# DO.net
KiCad netlist of a schematic drawn in Altium Designer
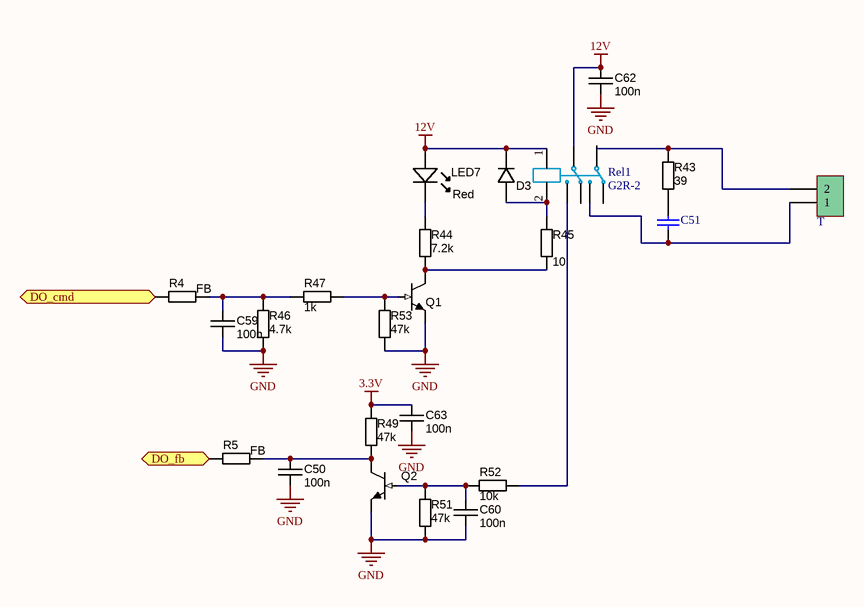
[diagram p0: DO.SchDoc]

(export (version "E")
  (design (tool "Eeschema 10.0.6"))
  (components
    (comp (ref "C50")
      (value "100n")
      (footprint "CAPC1608X90N")
      (description "Capacitor 0603")
      (fields (field (name "TOLERANCE") "±10%"))
      (libsource (lib "PBL - Capacitors") (part "CAPC_1n_0603_X7R_100V_10%"))
    )
    (comp (ref "C51")
      (value "~")
      (footprint "CAP14MM")
      (description "X1Y2 capacitor")
      (fields (field (name "PUBLISHER") "Altium Limited"))
      (libsource (lib "Miscellaneous Devices") (part "Cap Semi"))
    )
    (comp (ref "C59")
      (value "100n")
      (footprint "CAPC1608X90N")
      (description "Capacitor 0603")
      (fields (field (name "TOLERANCE") "±10%"))
      (libsource (lib "PBL - Capacitors") (part "CAPC_1n_0603_X7R_100V_10%"))
    )
    (comp (ref "C60")
      (value "100n")
      (footprint "CAPC1608X90N")
      (description "Capacitor 0603")
      (fields (field (name "TOLERANCE") "±10%"))
      (libsource (lib "PBL - Capacitors") (part "CAPC_1n_0603_X7R_100V_10%"))
    )
    (comp (ref "C62")
      (value "100n")
      (footprint "CAPC1608X90N")
      (description "Capacitor 0603")
      (fields (field (name "TOLERANCE") "±10%"))
      (libsource (lib "PBL - Capacitors") (part "CAPC_1n_0603_X7R_100V_10%"))
    )
    (comp (ref "C63")
      (value "100n")
      (footprint "CAPC1608X90N")
      (description "Capacitor 0603")
      (fields (field (name "TOLERANCE") "±10%"))
      (libsource (lib "PBL - Capacitors") (part "CAPC_1n_0603_X7R_100V_10%"))
    )
    (comp (ref "D3")
      (value "~")
      (footprint "SOD80, LL-34")
      (description "1n4148 minimelf")
      (libsource (lib "PBL - Diodes") (part "DIODE_100V_500mW_MELF"))
    )
    (comp (ref "LED7")
      (value "Red")
      (footprint "LED-0805-K")
      (description "LED 0805 Red")
      (fields (field (name "Comment") "LED B"))
      (libsource (lib "PBL - Light Sources") (part "LED_SMD_Green_0805_6mcd"))
    )
    (comp (ref "Q1")
      (value "~")
      (footprint "SOT-23_N")
      (description "BC817")
      (libsource (lib "PBL - Transistors") (part "NPN_MMBT2222A"))
    )
    (comp (ref "Q2")
      (value "~")
      (footprint "SOT-23_N")
      (description "BC817")
      (libsource (lib "PBL - Transistors") (part "NPN_MMBT2222A"))
    )
    (comp (ref "R4")
      (value "FB")
      (footprint "RESC1608X55N")
      (description "Resistor 0603")
      (fields (field (name "TOLERANCE") "±5%"))
      (libsource (lib "PBL - Resistors") (part "RES_2K2_0603_5%"))
    )
    (comp (ref "R5")
      (value "FB")
      (footprint "RESC1608X55N")
      (description "Resistor 0603")
      (fields (field (name "TOLERANCE") "±5%"))
      (libsource (lib "PBL - Resistors") (part "RES_2K2_0603_5%"))
    )
    (comp (ref "R43")
      (value "39")
      (footprint "RESTH_AXIAL-0.4")
      (description "Resistor .25w dip")
      (fields (field (name "TOLERANCE") "±5%"))
      (libsource (lib "PBL - Resistors") (part "RES_1K5_Axial_0.5W_5%"))
    )
    (comp (ref "R44")
      (value "7.2k")
      (footprint "RESC1608X55N")
      (description "Resistor 0603")
      (fields (field (name "TOLERANCE") "±5%"))
      (libsource (lib "") (part "RES_2K2_0603_5%_1"))
    )
    (comp (ref "R45")
      (value "10")
      (footprint "RESC3216X70N")
      (description "Resistor 1206")
      (fields (field (name "TOLERANCE") "±1%"))
      (libsource (lib "PBL - Resistors") (part "RES_1R_1206_1%"))
    )
    (comp (ref "R46")
      (value "4.7k")
      (footprint "RESC1608X55N")
      (description "Resistor 0603")
      (fields (field (name "TOLERANCE") "±5%"))
      (libsource (lib "") (part "RES_2K2_0603_5%_2"))
    )
    (comp (ref "R47")
      (value "1k")
      (footprint "RESC1608X55N")
      (description "Resistor 0603")
      (fields (field (name "TOLERANCE") "±5%"))
      (libsource (lib "PBL - Resistors") (part "RES_2K2_0603_5%"))
    )
    (comp (ref "R49")
      (value "47k")
      (footprint "RESC1608X55N")
      (description "Resistor 0603")
      (fields (field (name "TOLERANCE") "±5%"))
      (libsource (lib "PBL - Resistors") (part "RES_2K2_0603_5%"))
    )
    (comp (ref "R51")
      (value "47k")
      (footprint "RESC1608X55N")
      (description "Resistor 0603")
      (fields (field (name "TOLERANCE") "±5%"))
      (libsource (lib "PBL - Resistors") (part "RES_2K2_0603_5%"))
    )
    (comp (ref "R52")
      (value "10k")
      (footprint "RESC1608X55N")
      (description "Resistor 0603")
      (fields (field (name "TOLERANCE") "±5%"))
      (libsource (lib "") (part "RES_2K2_0603_5%_1"))
    )
    (comp (ref "R53")
      (value "47k")
      (footprint "RESC1608X55N")
      (description "Resistor 0603")
      (fields (field (name "TOLERANCE") "±5%"))
      (libsource (lib "PBL - Resistors") (part "RES_2K2_0603_5%"))
    )
    (comp (ref "Rel1")
      (value "G2R-2")
      (footprint "relay_G2R_2")
      (libsource (lib "sorour") (part "relay_G2R_2"))
    )
    (comp (ref "T")
      (value "Phoenix terminal 2 pin")
      (footprint "phoenix terminal 2")
      (description "Terminal 2 Pin")
      (fields (field (name "DESIGNER") "Seyed Mohsen Ghasemain") (field (name "E-MAIL") "picpars@gmail.com"))
      (libsource (lib "PicPars.com_usefully_Library") (part "Phoenix terminal 2"))
    )
  )
  (nets
    (net (code "1") (name "/DO_cmd") (class "Default")
      (node (ref "R4") (pin "1") (pinfunction "1_1") (pintype "passive"))
    )
    (net (code "2") (name "/DO_fb") (class "Default")
      (node (ref "R5") (pin "1") (pinfunction "1_1") (pintype "passive"))
    )
    (net (code "3") (name "3.3V") (class "Default")
      (node (ref "C63") (pin "2") (pintype "passive"))
      (node (ref "R49") (pin "2") (pinfunction "2_2") (pintype "passive"))
    )
    (net (code "4") (name "12V") (class "Default")
      (node (ref "C62") (pin "2") (pintype "passive"))
      (node (ref "D3") (pin "K") (pinfunction "K_K") (pintype "passive"))
      (node (ref "LED7") (pin "A") (pinfunction "A_A") (pintype "passive"))
      (node (ref "Rel1") (pin "1") (pintype "passive"))
      (node (ref "Rel1") (pin "3") (pintype "passive"))
    )
    (net (code "5") (name "GND") (class "Default")
      (node (ref "C50") (pin "1") (pintype "passive"))
      (node (ref "C59") (pin "1") (pintype "passive"))
      (node (ref "C60") (pin "1") (pintype "passive"))
      (node (ref "C62") (pin "1") (pintype "passive"))
      (node (ref "C63") (pin "1") (pintype "passive"))
      (node (ref "Q1") (pin "2") (pinfunction "E_2") (pintype "passive"))
      (node (ref "Q2") (pin "2") (pinfunction "E_2") (pintype "passive"))
      (node (ref "R46") (pin "1") (pinfunction "1_1") (pintype "passive"))
      (node (ref "R51") (pin "1") (pinfunction "1_1") (pintype "passive"))
      (node (ref "R53") (pin "1") (pinfunction "1_1") (pintype "passive"))
    )
    (net (code "6") (name "Net-(C51-Pad1)") (class "Default")
      (node (ref "C51") (pin "1") (pinfunction "1_1") (pintype "passive"))
      (node (ref "R43") (pin "2") (pinfunction "2_2") (pintype "passive"))
    )
    (net (code "7") (name "Net-(C51-Pad2)") (class "Default")
      (node (ref "C51") (pin "2") (pinfunction "2_2") (pintype "passive"))
      (node (ref "Rel1") (pin "7") (pintype "passive"))
      (node (ref "T") (pin "1") (pinfunction "1_1") (pintype "passive"))
    )
    (net (code "8") (name "Net-(C59-Pad2)") (class "Default")
      (node (ref "C59") (pin "2") (pintype "passive"))
      (node (ref "R4") (pin "2") (pinfunction "2_2") (pintype "passive"))
      (node (ref "R46") (pin "2") (pinfunction "2_2") (pintype "passive"))
      (node (ref "R47") (pin "1") (pinfunction "1_1") (pintype "passive"))
    )
    (net (code "9") (name "Net-(D3-PadA)") (class "Default")
      (node (ref "D3") (pin "A") (pinfunction "A_A") (pintype "passive"))
      (node (ref "R45") (pin "1") (pinfunction "1_1") (pintype "passive"))
      (node (ref "Rel1") (pin "2") (pintype "passive"))
    )
    (net (code "10") (name "Net-(LED7-PadK)") (class "Default")
      (node (ref "LED7") (pin "K") (pinfunction "K_K") (pintype "passive"))
      (node (ref "R44") (pin "1") (pinfunction "1_1") (pintype "passive"))
    )
    (net (code "11") (name "Net-(Q1-B)") (class "Default")
      (node (ref "Q1") (pin "1") (pinfunction "B_1") (pintype "input"))
      (node (ref "R47") (pin "2") (pinfunction "2_2") (pintype "passive"))
      (node (ref "R53") (pin "2") (pinfunction "2_2") (pintype "passive"))
    )
    (net (code "12") (name "Net-(Q1-C)") (class "Default")
      (node (ref "Q1") (pin "3") (pinfunction "C_3") (pintype "passive"))
      (node (ref "R44") (pin "2") (pinfunction "2_2") (pintype "passive"))
      (node (ref "R45") (pin "2") (pinfunction "2_2") (pintype "passive"))
    )
    (net (code "13") (name "Net-(Q2-B)") (class "Default")
      (node (ref "C60") (pin "2") (pintype "passive"))
      (node (ref "Q2") (pin "1") (pinfunction "B_1") (pintype "input"))
      (node (ref "R51") (pin "2") (pinfunction "2_2") (pintype "passive"))
      (node (ref "R52") (pin "2") (pinfunction "2_2") (pintype "passive"))
    )
    (net (code "14") (name "Net-(Q2-C)") (class "Default")
      (node (ref "C50") (pin "2") (pintype "passive"))
      (node (ref "Q2") (pin "3") (pinfunction "C_3") (pintype "passive"))
      (node (ref "R49") (pin "1") (pinfunction "1_1") (pintype "passive"))
      (node (ref "R5") (pin "2") (pinfunction "2_2") (pintype "passive"))
    )
    (net (code "15") (name "Net-(R43-Pad1)") (class "Default")
      (node (ref "R43") (pin "1") (pinfunction "1_1") (pintype "passive"))
      (node (ref "Rel1") (pin "4") (pintype "passive"))
      (node (ref "T") (pin "2") (pinfunction "2_2") (pintype "passive"))
    )
    (net (code "16") (name "Net-(R52-Pad1)") (class "Default")
      (node (ref "R52") (pin "1") (pinfunction "1_1") (pintype "passive"))
      (node (ref "Rel1") (pin "5") (pintype "passive"))
    )
    (net (code "17") (name "unconnected-(Rel1-Pad6)") (class "Default")
      (node (ref "Rel1") (pin "6") (pintype "passive"))
    )
    (net (code "18") (name "unconnected-(Rel1-Pad8)") (class "Default")
      (node (ref "Rel1") (pin "8") (pintype "passive"))
    )
  )
)
